# Lab10.net
KiCad netlist of a schematic drawn in Altium Designer
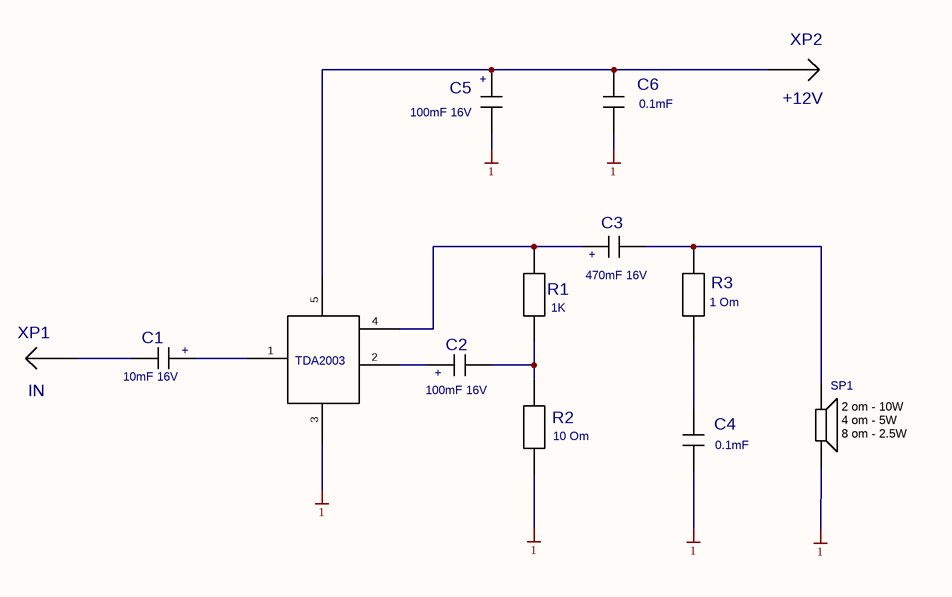
[diagram p0: Lab10.SCHDOC]

(export (version "E")
  (design (tool "Eeschema 10.0.6"))
  (components
    (comp (ref "1") (value "TDA2003") (footprint "TDA2003") (libsource (lib "*") (part "TDA2003")))
    (comp (ref "C1")
      (value "10mF 16V")
      (footprint "CAP2")
      (description "CAP2")
      (libsource (lib "*") (part "CAP2"))
    )
    (comp (ref "C2")
      (value "100mF 16V")
      (footprint "CAP2")
      (description "CAP2")
      (libsource (lib "*") (part "CAP2"))
    )
    (comp (ref "C3")
      (value "470mF 16V")
      (footprint "CAP2")
      (description "CAP2")
      (libsource (lib "*") (part "CAP2"))
    )
    (comp (ref "C4")
      (value "0.1mF")
      (footprint "CAP1")
      (description "CAP1")
      (libsource (lib "*") (part "CAP1"))
    )
    (comp (ref "C5")
      (value "100mF 16V")
      (footprint "CAP2")
      (description "CAP2")
      (libsource (lib "*") (part "CAP2"))
    )
    (comp (ref "C6")
      (value "0.1mF")
      (footprint "CAP1")
      (description "CAP1")
      (libsource (lib "*") (part "CAP1"))
    )
    (comp (ref "R1") (value "1K") (footprint "RES") (description "RES") (libsource (lib "*") (part "RES")))
    (comp (ref "R2") (value "10 Om") (footprint "RES") (description "RES") (libsource (lib "*") (part "RES")))
    (comp (ref "R3") (value "1 Om") (footprint "RES") (description "RES") (libsource (lib "*") (part "RES")))
    (comp (ref "SP1") (value "SPEAKER") (footprint "CAP1") (libsource (lib "*") (part "SPEAKER")))
    (comp (ref "XP1") (value "IN") (footprint "1PAD") (description "XP1") (libsource (lib "*") (part "XP1")))
    (comp (ref "XP2")
      (value "+12V")
      (footprint "1PAD")
      (description "XP1")
      (libsource (lib "*") (part "XP1"))
    )
  )
  (nets
    (net (code "1") (name "1") (class "Default")
      (node (ref "1") (pin "3") (pinfunction "3_3") (pintype "passive"))
      (node (ref "C4") (pin "1") (pinfunction "1_1") (pintype "passive"))
      (node (ref "C5") (pin "2") (pinfunction "2_2") (pintype "passive"))
      (node (ref "C6") (pin "1") (pinfunction "1_1") (pintype "passive"))
      (node (ref "R2") (pin "1") (pinfunction "1_1") (pintype "passive"))
      (node (ref "SP1") (pin "2") (pintype "passive"))
    )
    (net (code "2") (name "Net-(1-Pad1)") (class "Default")
      (node (ref "1") (pin "1") (pinfunction "1_1") (pintype "passive"))
      (node (ref "C1") (pin "1") (pinfunction "1_1") (pintype "passive"))
    )
    (net (code "3") (name "Net-(1-Pad2)") (class "Default")
      (node (ref "1") (pin "2") (pinfunction "2_2") (pintype "passive"))
      (node (ref "C2") (pin "1") (pinfunction "1_1") (pintype "passive"))
    )
    (net (code "4") (name "Net-(1-Pad4)") (class "Default")
      (node (ref "1") (pin "4") (pinfunction "4_4") (pintype "passive"))
      (node (ref "C3") (pin "1") (pinfunction "1_1") (pintype "passive"))
      (node (ref "R1") (pin "2") (pinfunction "2_2") (pintype "passive"))
    )
    (net (code "5") (name "Net-(C2-Pad2)") (class "Default")
      (node (ref "C2") (pin "2") (pinfunction "2_2") (pintype "passive"))
      (node (ref "R1") (pin "1") (pinfunction "1_1") (pintype "passive"))
      (node (ref "R2") (pin "2") (pinfunction "2_2") (pintype "passive"))
    )
    (net (code "6") (name "Net-(C3-Pad2)") (class "Default")
      (node (ref "C3") (pin "2") (pinfunction "2_2") (pintype "passive"))
      (node (ref "R3") (pin "2") (pinfunction "2_2") (pintype "passive"))
      (node (ref "SP1") (pin "1") (pintype "passive"))
    )
    (net (code "7") (name "Net-(C4-Pad2)") (class "Default")
      (node (ref "C4") (pin "2") (pinfunction "2_2") (pintype "passive"))
      (node (ref "R3") (pin "1") (pinfunction "1_1") (pintype "passive"))
    )
    (net (code "8") (name "Net-(XP1-A1)") (class "Default")
      (node (ref "C1") (pin "2") (pinfunction "2_2") (pintype "passive"))
      (node (ref "XP1") (pin "1") (pinfunction "A1_1") (pintype "passive"))
    )
    (net (code "9") (name "Net-(XP2-A1)") (class "Default")
      (node (ref "1") (pin "5") (pinfunction "5_5") (pintype "passive"))
      (node (ref "C5") (pin "1") (pinfunction "1_1") (pintype "passive"))
      (node (ref "C6") (pin "2") (pinfunction "2_2") (pintype "passive"))
      (node (ref "XP2") (pin "1") (pinfunction "A1_1") (pintype "passive"))
    )
  )
)
